# Attiny.net
KiCad netlist of a schematic drawn in Altium Designer
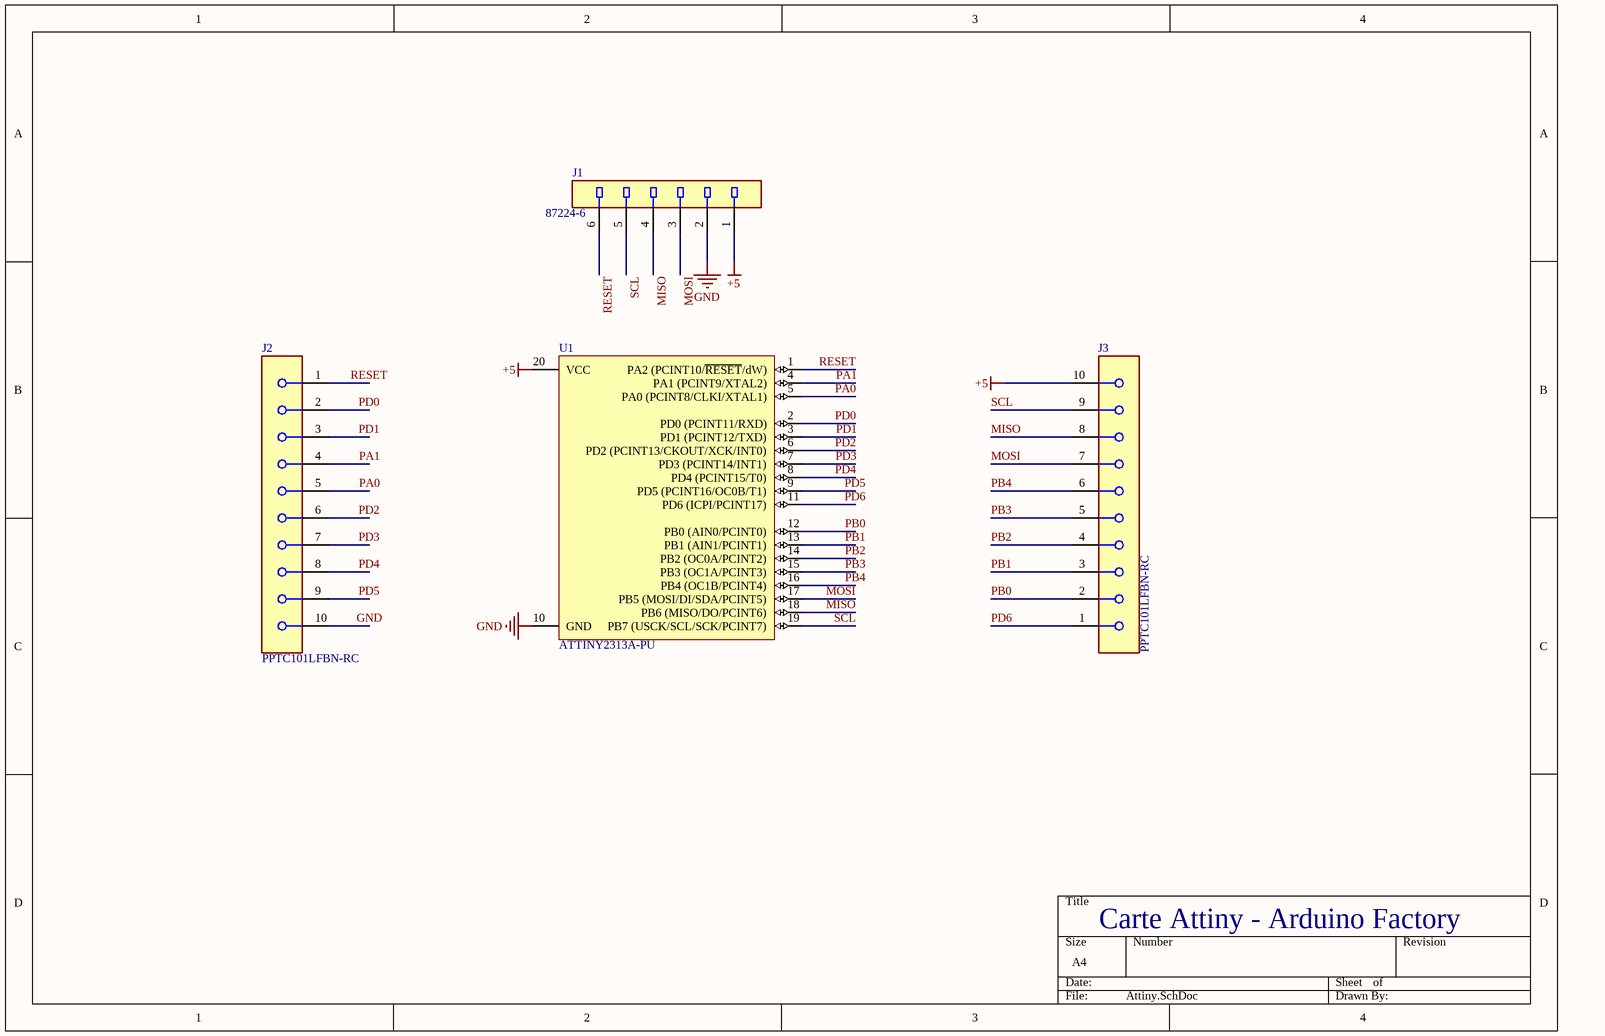
[diagram p0: Attiny.SchDoc]

(export (version "E")
  (design (tool "Eeschema 10.0.6"))
  (components
    (comp (ref "J1")
      (value "Conn_TE_87224-6_eec")
      (footprint "TE_87224-6_0")
      (description "CONN HEADER VERT .100 6POS 15AU")
      (fields
        (field (name "PART NUMBER") "87224-6")
        (field (name "MANUFACTURER") "TE")
        (field (name "MOUSER PART NUMBER") "571-872246")
      )
      (libsource (lib "Conn_TE_87224-6_eec") (part "Conn_TE_87224-6_eec"))
    )
    (comp (ref "J2")
      (value "Conn_Sullins_PPTC101LFBN-RC_eec")
      (footprint "Sullins_PPTC101LFBN-RC_0")
      (description "CONN HEADER FEMALE 10POS.1\" TIN")
      (fields
        (field (name "PART NUMBER") "PPTC101LFBN-RC")
        (field (name "MANUFACTURER") "Sullins")
        (field (name "OCTOPART PART NUMBER") "a3ed6ae3a4397c2a")
      )
      (libsource (lib "Conn_Sullins_PPTC101LFBN-RC_eec") (part "Conn_Sullins_PPTC101LFBN-RC_eec"))
    )
    (comp (ref "J3")
      (value "Conn_Sullins_PPTC101LFBN-RC_eec")
      (footprint "Sullins_PPTC101LFBN-RC_0")
      (description "CONN HEADER FEMALE 10POS.1\" TIN")
      (fields
        (field (name "PART NUMBER") "PPTC101LFBN-RC")
        (field (name "MANUFACTURER") "Sullins")
        (field (name "OCTOPART PART NUMBER") "a3ed6ae3a4397c2a")
      )
      (libsource (lib "") (part "Conn_Sullins_PPTC101LFBN-RC_eec_1"))
    )
    (comp (ref "U1")
      (value "ATTINY2313A-PU")
      (footprint "20P3")
      (libsource (lib "Microchip_Atmel_ATTINY2313A_PU") (part "ATTINY2313A-PU"))
    )
  )
  (nets
    (net (code "1") (name "+5") (class "Default")
      (node (ref "J1") (pin "1") (pinfunction "1_1") (pintype "passive"))
      (node (ref "J3") (pin "10") (pinfunction "10_10") (pintype "passive"))
      (node (ref "U1") (pin "20") (pinfunction "VCC_20") (pintype "power_in"))
    )
    (net (code "2") (name "/MISO") (class "Default")
      (node (ref "J1") (pin "4") (pinfunction "4_4") (pintype "passive"))
      (node (ref "J3") (pin "8") (pinfunction "8_8") (pintype "passive"))
      (node (ref "U1") (pin "18") (pinfunction "PB6_(MISO/DO/PCINT6)_18") (pintype "bidirectional"))
    )
    (net (code "3") (name "/MOSI") (class "Default")
      (node (ref "J1") (pin "3") (pinfunction "3_3") (pintype "passive"))
      (node (ref "J3") (pin "7") (pinfunction "7_7") (pintype "passive"))
      (node (ref "U1") (pin "17") (pinfunction "PB5_(MOSI/DI/SDA/PCINT5)_17") (pintype "bidirectional"))
    )
    (net (code "4") (name "/PA0") (class "Default")
      (node (ref "J2") (pin "5") (pinfunction "5_5") (pintype "passive"))
      (node (ref "U1") (pin "5") (pinfunction "PA0_(PCINT8/CLKI/XTAL1)_5") (pintype "bidirectional"))
    )
    (net (code "5") (name "/PA1") (class "Default")
      (node (ref "J2") (pin "4") (pinfunction "4_4") (pintype "passive"))
      (node (ref "U1") (pin "4") (pinfunction "PA1_(PCINT9/XTAL2)_4") (pintype "bidirectional"))
    )
    (net (code "6") (name "/PB0") (class "Default")
      (node (ref "J3") (pin "2") (pinfunction "2_2") (pintype "passive"))
      (node (ref "U1") (pin "12") (pinfunction "PB0_(AIN0/PCINT0)_12") (pintype "bidirectional"))
    )
    (net (code "7") (name "/PB1") (class "Default")
      (node (ref "J3") (pin "3") (pinfunction "3_3") (pintype "passive"))
      (node (ref "U1") (pin "13") (pinfunction "PB1_(AIN1/PCINT1)_13") (pintype "bidirectional"))
    )
    (net (code "8") (name "/PB2") (class "Default")
      (node (ref "J3") (pin "4") (pinfunction "4_4") (pintype "passive"))
      (node (ref "U1") (pin "14") (pinfunction "PB2_(OC0A/PCINT2)_14") (pintype "bidirectional"))
    )
    (net (code "9") (name "/PB3") (class "Default")
      (node (ref "J3") (pin "5") (pinfunction "5_5") (pintype "passive"))
      (node (ref "U1") (pin "15") (pinfunction "PB3_(OC1A/PCINT3)_15") (pintype "bidirectional"))
    )
    (net (code "10") (name "/PB4") (class "Default")
      (node (ref "J3") (pin "6") (pinfunction "6_6") (pintype "passive"))
      (node (ref "U1") (pin "16") (pinfunction "PB4_(OC1B/PCINT4)_16") (pintype "bidirectional"))
    )
    (net (code "11") (name "/PD0") (class "Default")
      (node (ref "J2") (pin "2") (pinfunction "2_2") (pintype "passive"))
      (node (ref "U1") (pin "2") (pinfunction "PD0_(PCINT11/RXD)_2") (pintype "bidirectional"))
    )
    (net (code "12") (name "/PD1") (class "Default")
      (node (ref "J2") (pin "3") (pinfunction "3_3") (pintype "passive"))
      (node (ref "U1") (pin "3") (pinfunction "PD1_(PCINT12/TXD)_3") (pintype "bidirectional"))
    )
    (net (code "13") (name "/PD2") (class "Default")
      (node (ref "J2") (pin "6") (pinfunction "6_6") (pintype "passive"))
      (node (ref "U1") (pin "6") (pinfunction "PD2_(PCINT13/CKOUT/XCK/INT0)_6") (pintype "bidirectional"))
    )
    (net (code "14") (name "/PD3") (class "Default")
      (node (ref "J2") (pin "7") (pinfunction "7_7") (pintype "passive"))
      (node (ref "U1") (pin "7") (pinfunction "PD3_(PCINT14/INT1)_7") (pintype "bidirectional"))
    )
    (net (code "15") (name "/PD4") (class "Default")
      (node (ref "J2") (pin "8") (pinfunction "8_8") (pintype "passive"))
      (node (ref "U1") (pin "8") (pinfunction "PD4_(PCINT15/T0)_8") (pintype "bidirectional"))
    )
    (net (code "16") (name "/PD5") (class "Default")
      (node (ref "J2") (pin "9") (pinfunction "9_9") (pintype "passive"))
      (node (ref "U1") (pin "9") (pinfunction "PD5_(PCINT16/OC0B/T1)_9") (pintype "bidirectional"))
    )
    (net (code "17") (name "/PD6") (class "Default")
      (node (ref "J3") (pin "1") (pinfunction "1_1") (pintype "passive"))
      (node (ref "U1") (pin "11") (pinfunction "PD6_(ICPI/PCINT17)_11") (pintype "bidirectional"))
    )
    (net (code "18") (name "/RESET") (class "Default")
      (node (ref "J1") (pin "6") (pinfunction "6_6") (pintype "passive"))
      (node (ref "J2") (pin "1") (pinfunction "1_1") (pintype "passive"))
      (node (ref "U1") (pin "1") (pinfunction "PA2_(PCINT10/~{RESET}/dW)_1") (pintype "bidirectional"))
    )
    (net (code "19") (name "/SCL") (class "Default")
      (node (ref "J1") (pin "5") (pinfunction "5_5") (pintype "passive"))
      (node (ref "J3") (pin "9") (pinfunction "9_9") (pintype "passive"))
      (node (ref "U1") (pin "19") (pinfunction "PB7_(USCK/SCL/SCK/PCINT7)_19") (pintype "bidirectional"))
    )
    (net (code "20") (name "GND") (class "Default")
      (node (ref "J1") (pin "2") (pinfunction "2_2") (pintype "passive"))
      (node (ref "J2") (pin "10") (pinfunction "10_10") (pintype "passive"))
      (node (ref "U1") (pin "10") (pinfunction "GND_10") (pintype "power_in"))
    )
  )
)
